# IO_and_Connectors.net
KiCad netlist of a schematic drawn in Altium Designer
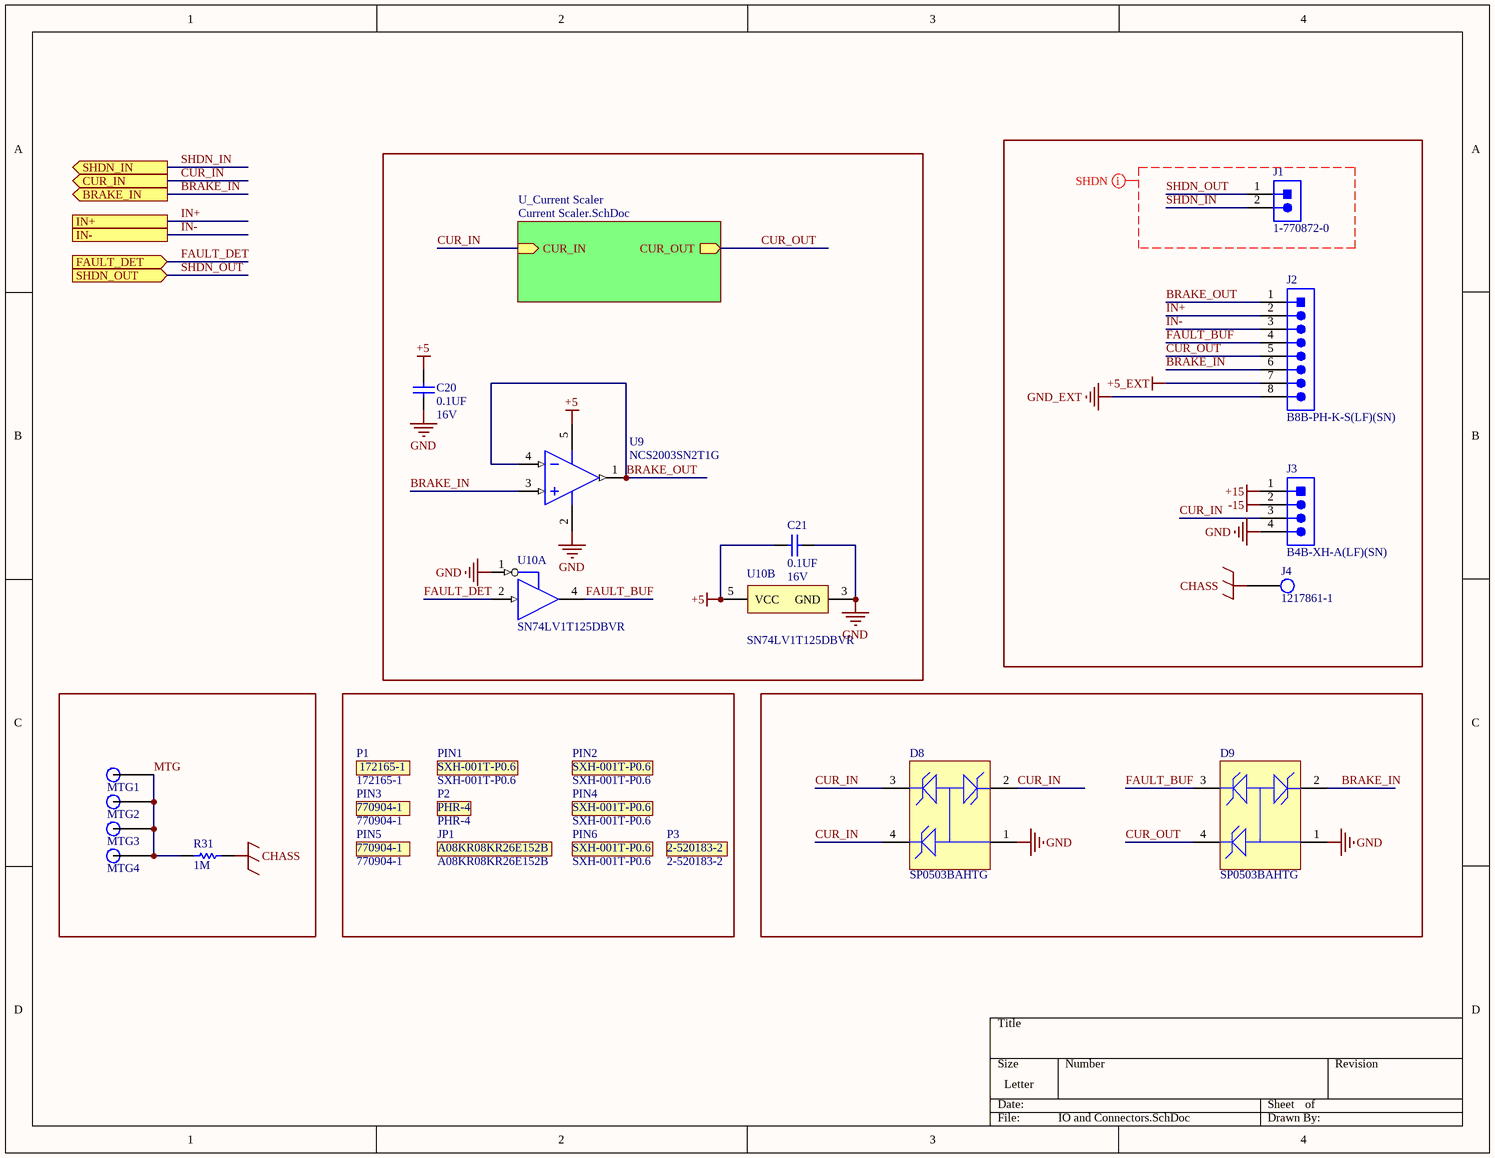
[diagram p0: IO and Connectors.SchDoc]

(export (version "E")
  (design (tool "Eeschema 10.0.6"))
  (components
    (comp (ref "C20")
      (value "CAP 0603 0.1UF 16V 10% X7R")
      (footprint "0603_CAP")
      (description "Capacitor Surface Mount 0603 Footprint 0.1UF 16V 10% Tolerance Ceramic X7R")
      (fields
        (field (name "VAL") "0.1UF")
        (field (name "VOL") "16V")
        (field (name "MANUFACTURER") "Various")
        (field (name "VOLTAGE") "16V")
      )
      (libsource (lib "Passive Components") (part "cap"))
    )
    (comp (ref "C21")
      (value "CAP 0603 0.1UF 16V 10% X7R")
      (footprint "0603_CAP")
      (description "Capacitor Surface Mount 0603 Footprint 0.1UF 16V 10% Tolerance Ceramic X7R")
      (fields
        (field (name "VAL") "0.1UF")
        (field (name "VOL") "16V")
        (field (name "MANUFACTURER") "Various")
        (field (name "VOLTAGE") "16V")
      )
      (libsource (lib "Passive Components") (part "cap"))
    )
    (comp (ref "D8")
      (value "SP0503BAHTG")
      (footprint "LFUS-SOT143-4_V")
      (description "TVS Diode Array, 30 pF, 30 KV, -40 to 85 degC, 4-Pin SOT143, RoHS, Tape and Reel")
      (fields (field (name "MANUFACTURER") "Littelfuse"))
      (libsource (lib "Altium Content Vault") (part "LFUS-SP0503BAHTG-SOT143-4"))
    )
    (comp (ref "D9")
      (value "SP0503BAHTG")
      (footprint "LFUS-SOT143-4_V")
      (description "TVS Diode Array, 30 pF, 30 KV, -40 to 85 degC, 4-Pin SOT143, RoHS, Tape and Reel")
      (fields (field (name "MANUFACTURER") "Littelfuse"))
      (libsource (lib "Altium Content Vault") (part "LFUS-SP0503BAHTG-SOT143-4"))
    )
    (comp (ref "J1")
      (value "1-770872-0")
      (footprint "CON2_1X2_P163_VM_ALT")
      (description "Connector Header Through Hole 2 position 0.163\" (4.14mm)")
      (fields (field (name "COPYRIGHT") "Copyright (C) 2018 Accelerated Designs. All rights reserved"))
      (libsource (lib "bspd parts") (part "1-770872-0"))
    )
    (comp (ref "J2")
      (value "B8B-PH-K-S(LF)(SN)")
      (footprint "B8B-PH-K")
      (description "Connector Header Through Hole 8 position 0.079\" (2.00mm)")
      (libsource (lib "bspd parts") (part "B8B-PH-K-S(LF)(SN)"))
    )
    (comp (ref "J3")
      (value "B4B-XH-A(LF)(SN)")
      (footprint "B4B-XH-A(LF)(SN)")
      (description "Connector Header Through Hole 4 position 0.098\" (2.50mm)")
      (fields (field (name "MANUFACTURER") "JST"))
      (libsource (lib "bspd parts") (part "B4B-XH-A(LF)(SN)"))
    )
    (comp (ref "J4")
      (value "1217861-1")
      (footprint "1217861-1")
      (description "CONN TAB .250 STR QC TIN PCB")
      (libsource (lib "bspd parts") (part "1217861-1"))
    )
    (comp (ref "JP1")
      (value "A08KR08KR26E152B")
      (description "8 Position Cable Assembly Rectangular Socket to Socket 0.500' (152.40mm, 6.00\")")
      (libsource (lib "bspd parts") (part "A08KR08KR26E152B"))
    )
    (comp (ref "MTG1")
      (value "PCB MTG M3")
      (footprint "MTG-M3")
      (description "PCB Mounting for M3 Screw")
      (libsource (lib "Hardware") (part "MTG"))
    )
    (comp (ref "MTG2")
      (value "PCB MTG M3")
      (footprint "MTG-M3")
      (description "PCB Mounting for M3 Screw")
      (libsource (lib "Hardware") (part "MTG"))
    )
    (comp (ref "MTG3")
      (value "PCB MTG M3")
      (footprint "MTG-M3")
      (description "PCB Mounting for M3 Screw")
      (libsource (lib "Hardware") (part "MTG"))
    )
    (comp (ref "MTG4")
      (value "PCB MTG M3")
      (footprint "MTG-M3")
      (description "PCB Mounting for M3 Screw")
      (libsource (lib "Hardware") (part "MTG"))
    )
    (comp (ref "P1")
      (value "172165-1")
      (description "2 Position Rectangular Housing Connector Plug Natural 0.163\" (4.14mm)")
      (libsource (lib "bspd parts") (part "172165-1"))
    )
    (comp (ref "P2")
      (value "PHR-4")
      (description "4 Position Rectangular Housing Connector Receptacle Natural 0.079\" (2.00mm)")
      (libsource (lib "bspd parts") (part "PHR-4"))
    )
    (comp (ref "P3")
      (value "2-520183-2")
      (description "0.250\" (6.35mm) Quick Connect Female 18-22 AWG Crimp Connector Fully Insulated")
      (libsource (lib "bspd parts") (part "2-520183-2"))
    )
    (comp (ref "PIN1")
      (value "SXH-001T-P0.6")
      (description "Socket Contact Tin 22-28 AWG Crimp Stamped")
      (libsource (lib "bspd parts") (part "SXH-001T-P0.6"))
    )
    (comp (ref "PIN2")
      (value "SXH-001T-P0.6")
      (description "Socket Contact Tin 22-28 AWG Crimp Stamped")
      (libsource (lib "bspd parts") (part "SXH-001T-P0.6"))
    )
    (comp (ref "PIN3")
      (value "770904-1")
      (description "Socket Contact  Crimp 18-22 AWG Stamped")
      (libsource (lib "bspd parts") (part "770904-1"))
    )
    (comp (ref "PIN4")
      (value "SXH-001T-P0.6")
      (description "Socket Contact Tin 22-28 AWG Crimp Stamped")
      (libsource (lib "bspd parts") (part "SXH-001T-P0.6"))
    )
    (comp (ref "PIN5")
      (value "770904-1")
      (description "Socket Contact  Crimp 18-22 AWG Stamped")
      (libsource (lib "bspd parts") (part "770904-1"))
    )
    (comp (ref "PIN6")
      (value "SXH-001T-P0.6")
      (description "Socket Contact Tin 22-28 AWG Crimp Stamped")
      (libsource (lib "bspd parts") (part "SXH-001T-P0.6"))
    )
    (comp (ref "R31")
      (value "1M")
      (footprint "RESC2013X60X35ML10T20")
      (fields (field (name "MANUFACTURER") "Yageo") (field (name "PART NUMBER") "RT0805BRE071ML"))
      (libsource (lib "Altium Content Vault") (part "RES"))
    )
    (comp (ref "U9")
      (value "NCS2003SN2T1G")
      (footprint "ONSC-TSOP-5-483-02_V")
      (fields (field (name "MANUFACTURER") "On Semiconductor"))
      (libsource (lib "Altium Content Vault") (part "ONSC-NCS2003-TSOP-5-483-02"))
    )
    (comp (ref "U10")
      (value "SN74LV1T125DBVR")
      (footprint "DBV0005A_M")
      (description "Single Power Supply, Single BUFFER GATE w/ 3-State Output (active low enable), DBV0005A, LARGE T&R")
      (fields
        (field (name "GENERIC PART NUMBER") "SN74LV1T125")
        (field (name "MANUFACTURER") "Texas Instruments")
      )
      (libsource (lib "Altium Content Vault") (part "TI-SN74AXXXX1X125-5"))
    )
  )
  (nets
    (net (code "1") (name "+5") (class "Default")
      (node (ref "C20") (pin "2") (pinfunction "2_2") (pintype "passive"))
      (node (ref "C21") (pin "2") (pinfunction "2_2") (pintype "passive"))
      (node (ref "U10") (pin "5") (pinfunction "VCC_5") (pintype "power_in"))
      (node (ref "U9") (pin "5") (pinfunction "VDD_5") (pintype "power_in"))
    )
    (net (code "2") (name "+5_EXT") (class "Default")
      (node (ref "J2") (pin "7") (pinfunction "7_7") (pintype "passive"))
    )
    (net (code "3") (name "+15") (class "Default")
      (node (ref "J3") (pin "1") (pinfunction "1_1") (pintype "passive"))
    )
    (net (code "4") (name "-15") (class "Default")
      (node (ref "J3") (pin "2") (pinfunction "2_2") (pintype "passive"))
    )
    (net (code "5") (name "/BRAKE_IN") (class "Default")
      (node (ref "D9") (pin "2") (pinfunction "2_2") (pintype "passive"))
      (node (ref "J2") (pin "6") (pinfunction "6_6") (pintype "passive"))
      (node (ref "U9") (pin "3") (pinfunction "IN+_3") (pintype "input"))
    )
    (net (code "6") (name "/BRAKE_OUT") (class "Default")
      (node (ref "J2") (pin "1") (pinfunction "1_1") (pintype "passive"))
      (node (ref "U9") (pin "1") (pinfunction "VOUT_1") (pintype "output"))
      (node (ref "U9") (pin "4") (pinfunction "IN-_4") (pintype "input"))
    )
    (net (code "7") (name "/CUR_IN") (class "Default")
      (node (ref "D8") (pin "2") (pinfunction "2_2") (pintype "passive"))
      (node (ref "D8") (pin "3") (pinfunction "3_3") (pintype "passive"))
      (node (ref "D8") (pin "4") (pinfunction "4_4") (pintype "passive"))
      (node (ref "J3") (pin "3") (pinfunction "3_3") (pintype "passive"))
    )
    (net (code "8") (name "/CUR_OUT") (class "Default")
      (node (ref "D9") (pin "4") (pinfunction "4_4") (pintype "passive"))
      (node (ref "J2") (pin "5") (pinfunction "5_5") (pintype "passive"))
    )
    (net (code "9") (name "/FAULT_BUF") (class "Default")
      (node (ref "D9") (pin "3") (pinfunction "3_3") (pintype "passive"))
      (node (ref "J2") (pin "4") (pinfunction "4_4") (pintype "passive"))
      (node (ref "U10") (pin "4") (pinfunction "Y_4") (pintype "tri_state"))
    )
    (net (code "10") (name "/FAULT_DET") (class "Default")
      (node (ref "U10") (pin "2") (pinfunction "A_2") (pintype "input"))
    )
    (net (code "11") (name "/IN+") (class "Default")
      (node (ref "J2") (pin "2") (pinfunction "2_2") (pintype "passive"))
    )
    (net (code "12") (name "/IN-") (class "Default")
      (node (ref "J2") (pin "3") (pinfunction "3_3") (pintype "passive"))
    )
    (net (code "13") (name "/MTG") (class "Default")
      (node (ref "MTG1") (pin "1") (pinfunction "1_1") (pintype "passive"))
      (node (ref "MTG2") (pin "1") (pinfunction "1_1") (pintype "passive"))
      (node (ref "MTG3") (pin "1") (pinfunction "1_1") (pintype "passive"))
      (node (ref "MTG4") (pin "1") (pinfunction "1_1") (pintype "passive"))
      (node (ref "R31") (pin "2") (pinfunction "2_2") (pintype "passive"))
    )
    (net (code "14") (name "/SHDN_IN") (class "Default")
      (node (ref "J1") (pin "2") (pinfunction "2_2") (pintype "passive"))
    )
    (net (code "15") (name "/SHDN_OUT") (class "Default")
      (node (ref "J1") (pin "1") (pinfunction "1_1") (pintype "passive"))
    )
    (net (code "16") (name "CHASS") (class "Default")
      (node (ref "J4") (pin "1") (pinfunction "1_1") (pintype "passive"))
      (node (ref "R31") (pin "1") (pinfunction "1_1") (pintype "passive"))
    )
    (net (code "17") (name "GND") (class "Default")
      (node (ref "C20") (pin "1") (pinfunction "1_1") (pintype "passive"))
      (node (ref "C21") (pin "1") (pinfunction "1_1") (pintype "passive"))
      (node (ref "D8") (pin "1") (pinfunction "1_1") (pintype "passive"))
      (node (ref "D9") (pin "1") (pinfunction "1_1") (pintype "passive"))
      (node (ref "J3") (pin "4") (pinfunction "4_4") (pintype "passive"))
      (node (ref "U10") (pin "1") (pinfunction "~{OE}_1") (pintype "input"))
      (node (ref "U10") (pin "3") (pinfunction "GND_3") (pintype "power_in"))
      (node (ref "U9") (pin "2") (pinfunction "VSS_2") (pintype "power_in"))
    )
    (net (code "18") (name "GND_EXT") (class "Default")
      (node (ref "J2") (pin "8") (pinfunction "8_8") (pintype "passive"))
    )
  )
)
